# esp8266.net
KiCad netlist of a schematic drawn in EAGLE
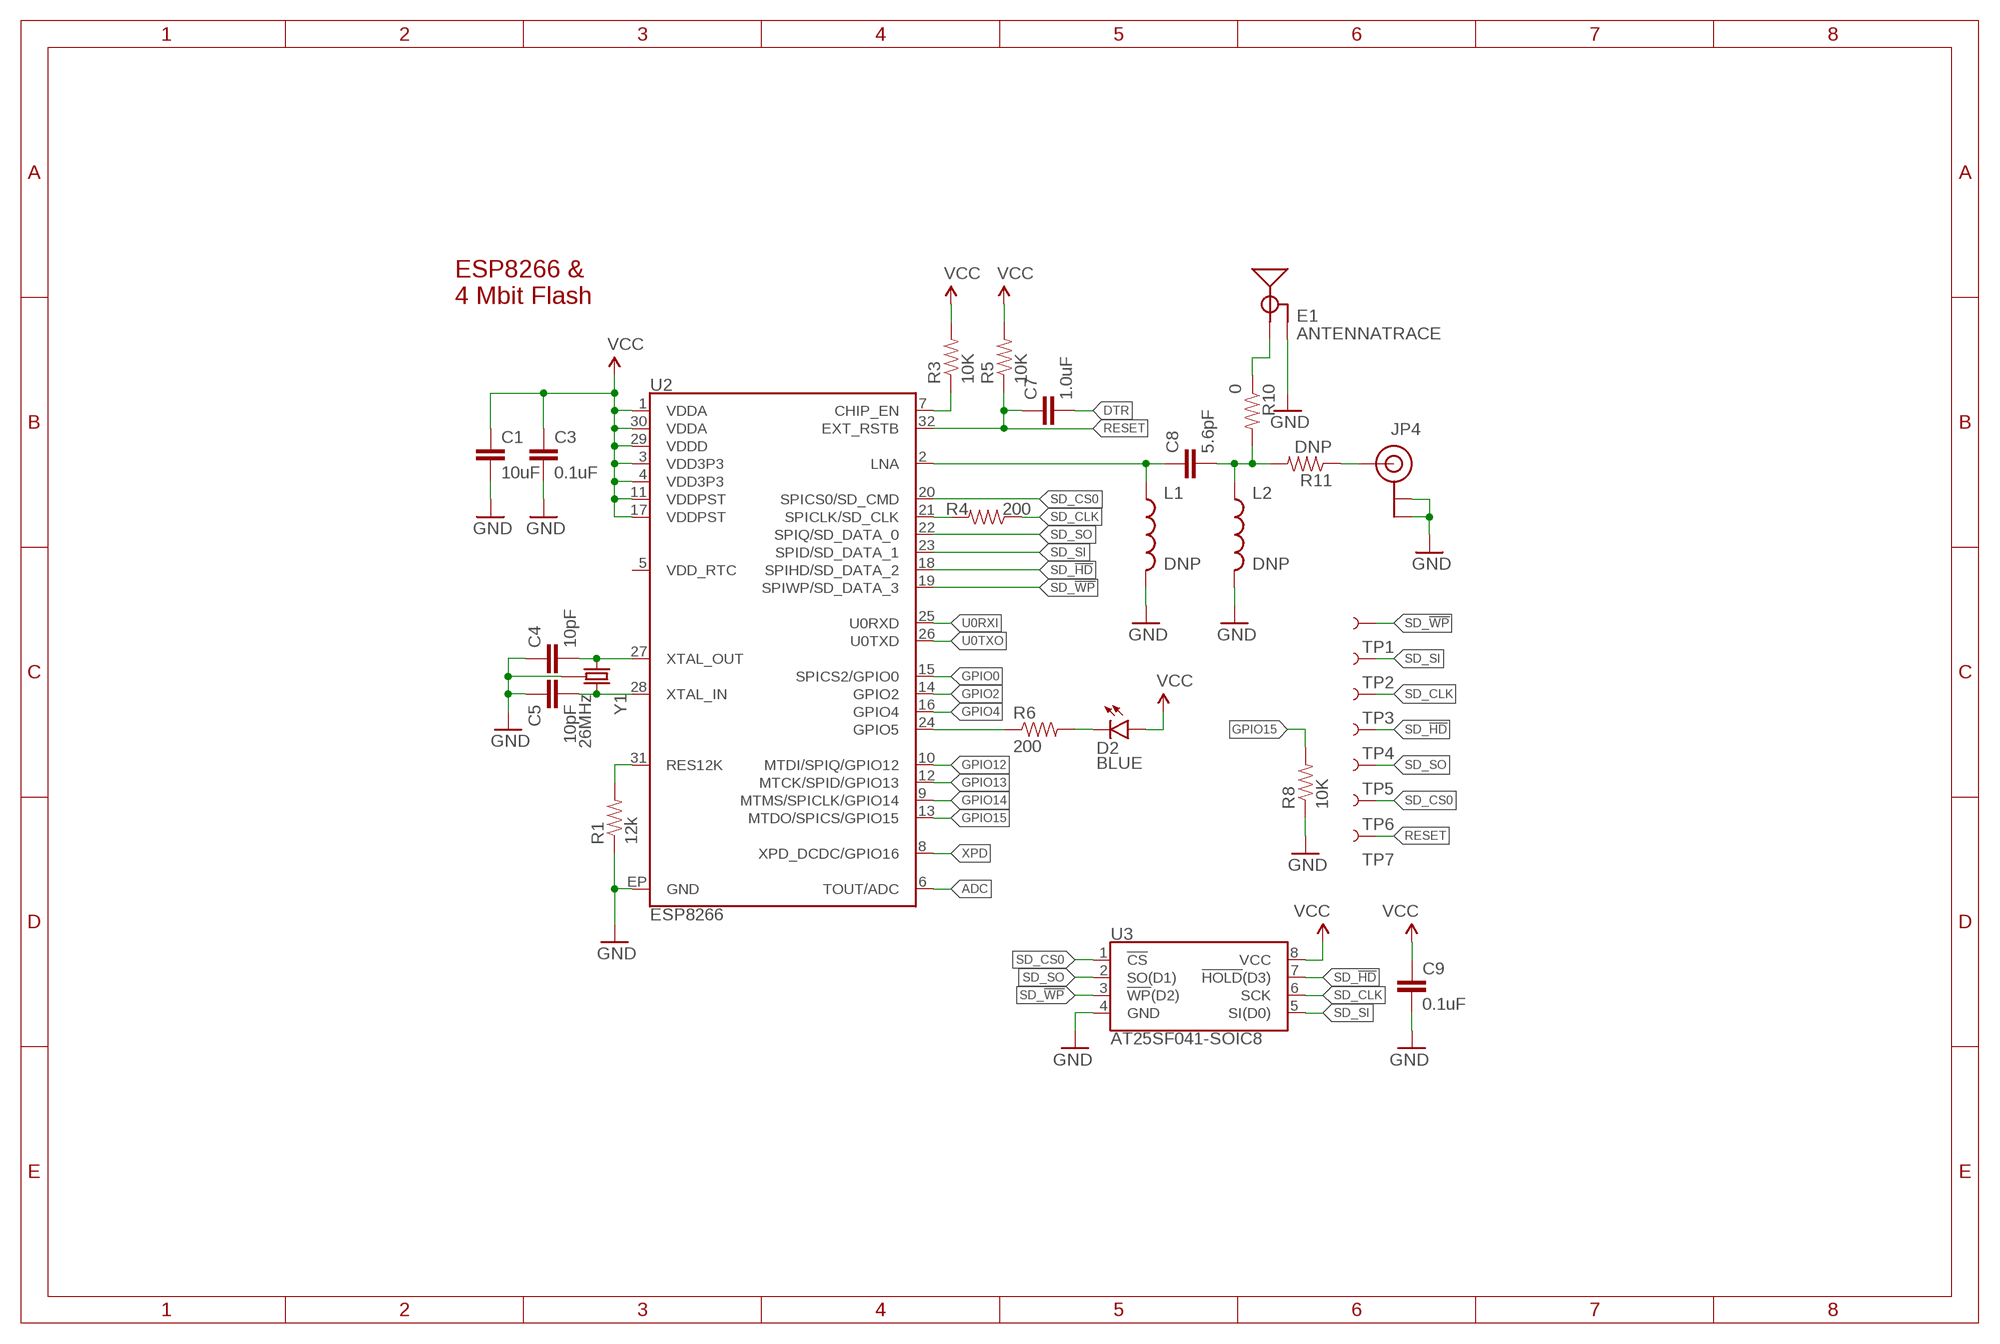
[diagram p0: schematic, sheet 1]

(export (version "E")
  (design (tool "Eeschema 10.0.6"))
  (components
    (comp (ref "C1")
      (value "10uF")
      (footprint "eagle-import:0603-CAP")
      (libsource (lib "eagle-import") (part "10UF-6.3V-20%(0603)"))
    )
    (comp (ref "C3")
      (value "0.1uF")
      (footprint "eagle-import:0603-CAP")
      (libsource (lib "eagle-import") (part "0.1UF-25V(+80/-20%)(0603)"))
    )
    (comp (ref "C4")
      (value "10pF")
      (footprint "eagle-import:0603-CAP")
      (libsource (lib "eagle-import") (part "10PF-50V-5%(0603)"))
    )
    (comp (ref "C5")
      (value "10pF")
      (footprint "eagle-import:0603-CAP")
      (libsource (lib "eagle-import") (part "10PF-50V-5%(0603)"))
    )
    (comp (ref "C7")
      (value "1.0uF")
      (footprint "eagle-import:0603-CAP")
      (libsource (lib "eagle-import") (part "1.0UF-16V-10%(0603)"))
    )
    (comp (ref "C8")
      (value "5.6pF")
      (footprint "eagle-import:0603-CAP")
      (libsource (lib "eagle-import") (part "CAP0603-CAP"))
    )
    (comp (ref "C9")
      (value "0.1uF")
      (footprint "eagle-import:0603-CAP")
      (libsource (lib "eagle-import") (part "0.1UF-25V(+80/-20%)(0603)"))
    )
    (comp (ref "D2")
      (value "BLUE")
      (footprint "eagle-import:LED-0603")
      (libsource (lib "eagle-import") (part "LED-BLUE0603"))
    )
    (comp (ref "E1")
      (value "ANTENNATRACE")
      (footprint "eagle-import:TRACE_ANTENNA_2.4GHZ_25.7MM")
      (libsource (lib "eagle-import") (part "ANTENNATRACE"))
    )
    (comp (ref "JP4")
      (value "U.FL")
      (footprint "eagle-import:U.FL")
      (libsource (lib "eagle-import") (part "U.FL"))
    )
    (comp (ref "L1")
      (value "DNP")
      (footprint "eagle-import:0603")
      (libsource (lib "eagle-import") (part "INDUCTOR0603"))
    )
    (comp (ref "L2")
      (value "DNP")
      (footprint "eagle-import:0603")
      (libsource (lib "eagle-import") (part "INDUCTOR0603"))
    )
    (comp (ref "R1")
      (value "12k")
      (footprint "eagle-import:0603-RES")
      (libsource (lib "eagle-import") (part "12KOHM-1/10W-1%(0603)"))
    )
    (comp (ref "R3")
      (value "10K")
      (footprint "eagle-import:0603-RES")
      (libsource (lib "eagle-import") (part "10KOHM1/10W1%(0603)0603"))
    )
    (comp (ref "R4")
      (value "200")
      (footprint "eagle-import:0603-RES")
      (libsource (lib "eagle-import") (part "200OHM1/10W1%(0603)"))
    )
    (comp (ref "R5")
      (value "10K")
      (footprint "eagle-import:0603-RES")
      (libsource (lib "eagle-import") (part "10KOHM1/10W1%(0603)0603"))
    )
    (comp (ref "R6")
      (value "200")
      (footprint "eagle-import:0603-RES")
      (libsource (lib "eagle-import") (part "200OHM1/10W1%(0603)"))
    )
    (comp (ref "R8")
      (value "10K")
      (footprint "eagle-import:0603-RES")
      (libsource (lib "eagle-import") (part "10KOHM1/10W1%(0603)0603"))
    )
    (comp (ref "R10")
      (value "0")
      (footprint "eagle-import:0603")
      (libsource (lib "eagle-import") (part "0OHM1/10W5%(0603)"))
    )
    (comp (ref "R11")
      (value "DNP")
      (footprint "eagle-import:0603-RES")
      (libsource (lib "eagle-import") (part "RESISTOR0603-RES"))
    )
    (comp (ref "TP1")
      (value "TEST-POINT3X5")
      (footprint "eagle-import:PAD.03X.05")
      (libsource (lib "eagle-import") (part "TEST-POINT3X5"))
    )
    (comp (ref "TP2")
      (value "TEST-POINT3X5")
      (footprint "eagle-import:PAD.03X.05")
      (libsource (lib "eagle-import") (part "TEST-POINT3X5"))
    )
    (comp (ref "TP3")
      (value "TEST-POINT3X5")
      (footprint "eagle-import:PAD.03X.05")
      (libsource (lib "eagle-import") (part "TEST-POINT3X5"))
    )
    (comp (ref "TP4")
      (value "TEST-POINT3X5")
      (footprint "eagle-import:PAD.03X.05")
      (libsource (lib "eagle-import") (part "TEST-POINT3X5"))
    )
    (comp (ref "TP5")
      (value "TEST-POINT3X5")
      (footprint "eagle-import:PAD.03X.05")
      (libsource (lib "eagle-import") (part "TEST-POINT3X5"))
    )
    (comp (ref "TP6")
      (value "TEST-POINT3X5")
      (footprint "eagle-import:PAD.03X.05")
      (libsource (lib "eagle-import") (part "TEST-POINT3X5"))
    )
    (comp (ref "TP7")
      (value "TEST-POINT3X5")
      (footprint "eagle-import:PAD.03X.05")
      (libsource (lib "eagle-import") (part "TEST-POINT3X5"))
    )
    (comp (ref "U2")
      (value "ESP8266")
      (footprint "eagle-import:QFN32")
      (libsource (lib "eagle-import") (part "ESP8266"))
    )
    (comp (ref "U3")
      (value "AT25SF041-SOIC8")
      (footprint "eagle-import:SO08")
      (libsource (lib "eagle-import") (part "AT25SF041-SOIC8"))
    )
    (comp (ref "Y1")
      (value "26MHz")
      (footprint "eagle-import:CRYSTAL-SMD-3.2X2.5")
      (libsource (lib "eagle-import") (part "CRYSTAL-GROUNDED3.2X2.5"))
    )
  )
  (nets
    (net (code "1") (name "/SD_~{HD}") (class "Default")
      (node (ref "TP4") (pin "P$1") (pinfunction "1_P$1") (pintype "bidirectional"))
      (node (ref "U2") (pin "18") (pinfunction "SPIHD/SD_DATA_2_18") (pintype "bidirectional"))
      (node (ref "U3") (pin "7") (pinfunction "~{HOLD}(D3)_7") (pintype "bidirectional"))
    )
    (net (code "2") (name "/SD_~{WP}") (class "Default")
      (node (ref "TP1") (pin "P$1") (pinfunction "1_P$1") (pintype "bidirectional"))
      (node (ref "U2") (pin "19") (pinfunction "SPIWP/SD_DATA_3_19") (pintype "bidirectional"))
      (node (ref "U3") (pin "3") (pinfunction "~{WP}(D2)_3") (pintype "bidirectional"))
    )
    (net (code "3") (name "ADC") (class "Default")
      (node (ref "U2") (pin "6") (pinfunction "TOUT/ADC_6") (pintype "bidirectional"))
    )
    (net (code "4") (name "DTR") (class "Default")
      (node (ref "C7") (pin "2") (pinfunction "2_2") (pintype "passive"))
    )
    (net (code "5") (name "GND") (class "Default")
      (node (ref "C1") (pin "2") (pinfunction "2_2") (pintype "passive"))
      (node (ref "C3") (pin "2") (pinfunction "2_2") (pintype "passive"))
      (node (ref "C4") (pin "1") (pinfunction "1_1") (pintype "passive"))
      (node (ref "C5") (pin "1") (pinfunction "1_1") (pintype "passive"))
      (node (ref "C9") (pin "2") (pinfunction "2_2") (pintype "passive"))
      (node (ref "E1") (pin "GND") (pinfunction "GND_GND") (pintype "bidirectional"))
      (node (ref "E1") (pin "GND2") (pinfunction "GND_GND2") (pintype "bidirectional"))
      (node (ref "JP4") (pin "P$1") (pinfunction "GND_P$1") (pintype "bidirectional"))
      (node (ref "JP4") (pin "P$2") (pinfunction "GND_P$2") (pintype "bidirectional"))
      (node (ref "L1") (pin "2") (pinfunction "2_2") (pintype "passive"))
      (node (ref "L2") (pin "2") (pinfunction "2_2") (pintype "passive"))
      (node (ref "R1") (pin "1") (pinfunction "1_1") (pintype "passive"))
      (node (ref "R8") (pin "1") (pinfunction "1_1") (pintype "passive"))
      (node (ref "U2") (pin "EP") (pinfunction "GND_EP") (pintype "bidirectional"))
      (node (ref "U3") (pin "4") (pinfunction "GND_4") (pintype "bidirectional"))
      (node (ref "Y1") (pin "2") (pinfunction "GND_2") (pintype "passive"))
      (node (ref "Y1") (pin "4") (pinfunction "GND_4") (pintype "passive"))
    )
    (net (code "6") (name "GPIO0") (class "Default")
      (node (ref "U2") (pin "15") (pinfunction "SPICS2/GPIO0_15") (pintype "bidirectional"))
    )
    (net (code "7") (name "GPIO2") (class "Default")
      (node (ref "U2") (pin "14") (pinfunction "GPIO2_14") (pintype "bidirectional"))
    )
    (net (code "8") (name "GPIO4") (class "Default")
      (node (ref "U2") (pin "16") (pinfunction "GPIO4_16") (pintype "bidirectional"))
    )
    (net (code "9") (name "GPIO12") (class "Default")
      (node (ref "U2") (pin "10") (pinfunction "MTDI/SPIQ/GPIO12_10") (pintype "bidirectional"))
    )
    (net (code "10") (name "GPIO13") (class "Default")
      (node (ref "U2") (pin "12") (pinfunction "MTCK/SPID/GPIO13_12") (pintype "bidirectional"))
    )
    (net (code "11") (name "GPIO14") (class "Default")
      (node (ref "U2") (pin "9") (pinfunction "MTMS/SPICLK/GPIO14_9") (pintype "bidirectional"))
    )
    (net (code "12") (name "GPIO15") (class "Default")
      (node (ref "R8") (pin "2") (pinfunction "2_2") (pintype "passive"))
      (node (ref "U2") (pin "13") (pinfunction "MTDO/SPICS/GPIO15_13") (pintype "bidirectional"))
    )
    (net (code "13") (name "Net-(C8-Pad2)") (class "Default")
      (node (ref "C8") (pin "2") (pinfunction "2_2") (pintype "passive"))
      (node (ref "L2") (pin "1") (pinfunction "1_1") (pintype "passive"))
      (node (ref "R10") (pin "2") (pinfunction "2_2") (pintype "passive"))
      (node (ref "R11") (pin "2") (pinfunction "2_2") (pintype "passive"))
    )
    (net (code "14") (name "Net-(D2-PadC)") (class "Default")
      (node (ref "D2") (pin "C") (pinfunction "C_C") (pintype "passive"))
      (node (ref "R6") (pin "2") (pinfunction "2_2") (pintype "passive"))
    )
    (net (code "15") (name "Net-(E1-SIGNAL)") (class "Default")
      (node (ref "E1") (pin "ANT") (pinfunction "SIGNAL_ANT") (pintype "bidirectional"))
      (node (ref "R10") (pin "1") (pinfunction "1_1") (pintype "passive"))
    )
    (net (code "16") (name "Net-(JP4-SIGNAL)") (class "Default")
      (node (ref "JP4") (pin "P$3") (pinfunction "SIGNAL_P$3") (pintype "bidirectional"))
      (node (ref "R11") (pin "1") (pinfunction "1_1") (pintype "passive"))
    )
    (net (code "17") (name "Net-(U2-CHIP_EN)") (class "Default")
      (node (ref "R3") (pin "1") (pinfunction "1_1") (pintype "passive"))
      (node (ref "U2") (pin "7") (pinfunction "CHIP_EN_7") (pintype "bidirectional"))
    )
    (net (code "18") (name "Net-(U2-GPIO5)") (class "Default")
      (node (ref "R6") (pin "1") (pinfunction "1_1") (pintype "passive"))
      (node (ref "U2") (pin "24") (pinfunction "GPIO5_24") (pintype "bidirectional"))
    )
    (net (code "19") (name "Net-(U2-LNA)") (class "Default")
      (node (ref "C8") (pin "1") (pinfunction "1_1") (pintype "passive"))
      (node (ref "L1") (pin "1") (pinfunction "1_1") (pintype "passive"))
      (node (ref "U2") (pin "2") (pinfunction "LNA_2") (pintype "bidirectional"))
    )
    (net (code "20") (name "Net-(U2-RES12K)") (class "Default")
      (node (ref "R1") (pin "2") (pinfunction "2_2") (pintype "passive"))
      (node (ref "U2") (pin "31") (pinfunction "RES12K_31") (pintype "bidirectional"))
    )
    (net (code "21") (name "Net-(U2-SPICLK{slash}SD_CLK)") (class "Default")
      (node (ref "R4") (pin "2") (pinfunction "2_2") (pintype "passive"))
      (node (ref "U2") (pin "21") (pinfunction "SPICLK/SD_CLK_21") (pintype "bidirectional"))
    )
    (net (code "22") (name "Net-(U2-XTAL_IN)") (class "Default")
      (node (ref "C5") (pin "2") (pinfunction "2_2") (pintype "passive"))
      (node (ref "U2") (pin "28") (pinfunction "XTAL_IN_28") (pintype "bidirectional"))
      (node (ref "Y1") (pin "3") (pinfunction "2_3") (pintype "passive"))
    )
    (net (code "23") (name "Net-(U2-XTAL_OUT)") (class "Default")
      (node (ref "C4") (pin "2") (pinfunction "2_2") (pintype "passive"))
      (node (ref "U2") (pin "27") (pinfunction "XTAL_OUT_27") (pintype "bidirectional"))
      (node (ref "Y1") (pin "1") (pinfunction "1_1") (pintype "passive"))
    )
    (net (code "24") (name "RESET") (class "Default")
      (node (ref "C7") (pin "1") (pinfunction "1_1") (pintype "passive"))
      (node (ref "R5") (pin "1") (pinfunction "1_1") (pintype "passive"))
      (node (ref "TP7") (pin "P$1") (pinfunction "1_P$1") (pintype "bidirectional"))
      (node (ref "U2") (pin "32") (pinfunction "EXT_RSTB_32") (pintype "bidirectional"))
    )
    (net (code "25") (name "SD_CLK") (class "Default")
      (node (ref "R4") (pin "1") (pinfunction "1_1") (pintype "passive"))
      (node (ref "TP3") (pin "P$1") (pinfunction "1_P$1") (pintype "bidirectional"))
      (node (ref "U3") (pin "6") (pinfunction "SCK_6") (pintype "bidirectional"))
    )
    (net (code "26") (name "SD_CS0") (class "Default")
      (node (ref "TP6") (pin "P$1") (pinfunction "1_P$1") (pintype "bidirectional"))
      (node (ref "U2") (pin "20") (pinfunction "SPICS0/SD_CMD_20") (pintype "bidirectional"))
      (node (ref "U3") (pin "1") (pinfunction "~{CS}_1") (pintype "bidirectional"))
    )
    (net (code "27") (name "SD_SI") (class "Default")
      (node (ref "TP2") (pin "P$1") (pinfunction "1_P$1") (pintype "bidirectional"))
      (node (ref "U2") (pin "23") (pinfunction "SPID/SD_DATA_1_23") (pintype "bidirectional"))
      (node (ref "U3") (pin "5") (pinfunction "SI(D0)_5") (pintype "bidirectional"))
    )
    (net (code "28") (name "SD_SO") (class "Default")
      (node (ref "TP5") (pin "P$1") (pinfunction "1_P$1") (pintype "bidirectional"))
      (node (ref "U2") (pin "22") (pinfunction "SPIQ/SD_DATA_0_22") (pintype "bidirectional"))
      (node (ref "U3") (pin "2") (pinfunction "SO(D1)_2") (pintype "bidirectional"))
    )
    (net (code "29") (name "U0RXI") (class "Default")
      (node (ref "U2") (pin "25") (pinfunction "U0RXD_25") (pintype "bidirectional"))
    )
    (net (code "30") (name "U0TXO") (class "Default")
      (node (ref "U2") (pin "26") (pinfunction "U0TXD_26") (pintype "bidirectional"))
    )
    (net (code "31") (name "VCC") (class "Default")
      (node (ref "C1") (pin "1") (pinfunction "1_1") (pintype "passive"))
      (node (ref "C3") (pin "1") (pinfunction "1_1") (pintype "passive"))
      (node (ref "C9") (pin "1") (pinfunction "1_1") (pintype "passive"))
      (node (ref "D2") (pin "A") (pinfunction "A_A") (pintype "passive"))
      (node (ref "R3") (pin "2") (pinfunction "2_2") (pintype "passive"))
      (node (ref "R5") (pin "2") (pinfunction "2_2") (pintype "passive"))
      (node (ref "U2") (pin "1") (pinfunction "VDDA_1") (pintype "bidirectional"))
      (node (ref "U2") (pin "11") (pinfunction "VDDPST_11") (pintype "bidirectional"))
      (node (ref "U2") (pin "17") (pinfunction "VDDPST_17") (pintype "bidirectional"))
      (node (ref "U2") (pin "29") (pinfunction "VDDD_29") (pintype "bidirectional"))
      (node (ref "U2") (pin "3") (pinfunction "VDD3P3_3") (pintype "bidirectional"))
      (node (ref "U2") (pin "30") (pinfunction "VDDA_30") (pintype "bidirectional"))
      (node (ref "U2") (pin "4") (pinfunction "VDD3P3_4") (pintype "bidirectional"))
      (node (ref "U3") (pin "8") (pinfunction "VCC_8") (pintype "bidirectional"))
    )
    (net (code "32") (name "XPD") (class "Default")
      (node (ref "U2") (pin "8") (pinfunction "XPD_DCDC/GPIO16_8") (pintype "bidirectional"))
    )
    (net (code "33") (name "unconnected-(U2-VDD_RTC-Pad5)") (class "Default")
      (node (ref "U2") (pin "5") (pinfunction "VDD_RTC_5") (pintype "bidirectional"))
    )
  )
)
